# SOC_-_MCU_DOMAIN.net
KiCad netlist of a schematic drawn in Altium Designer
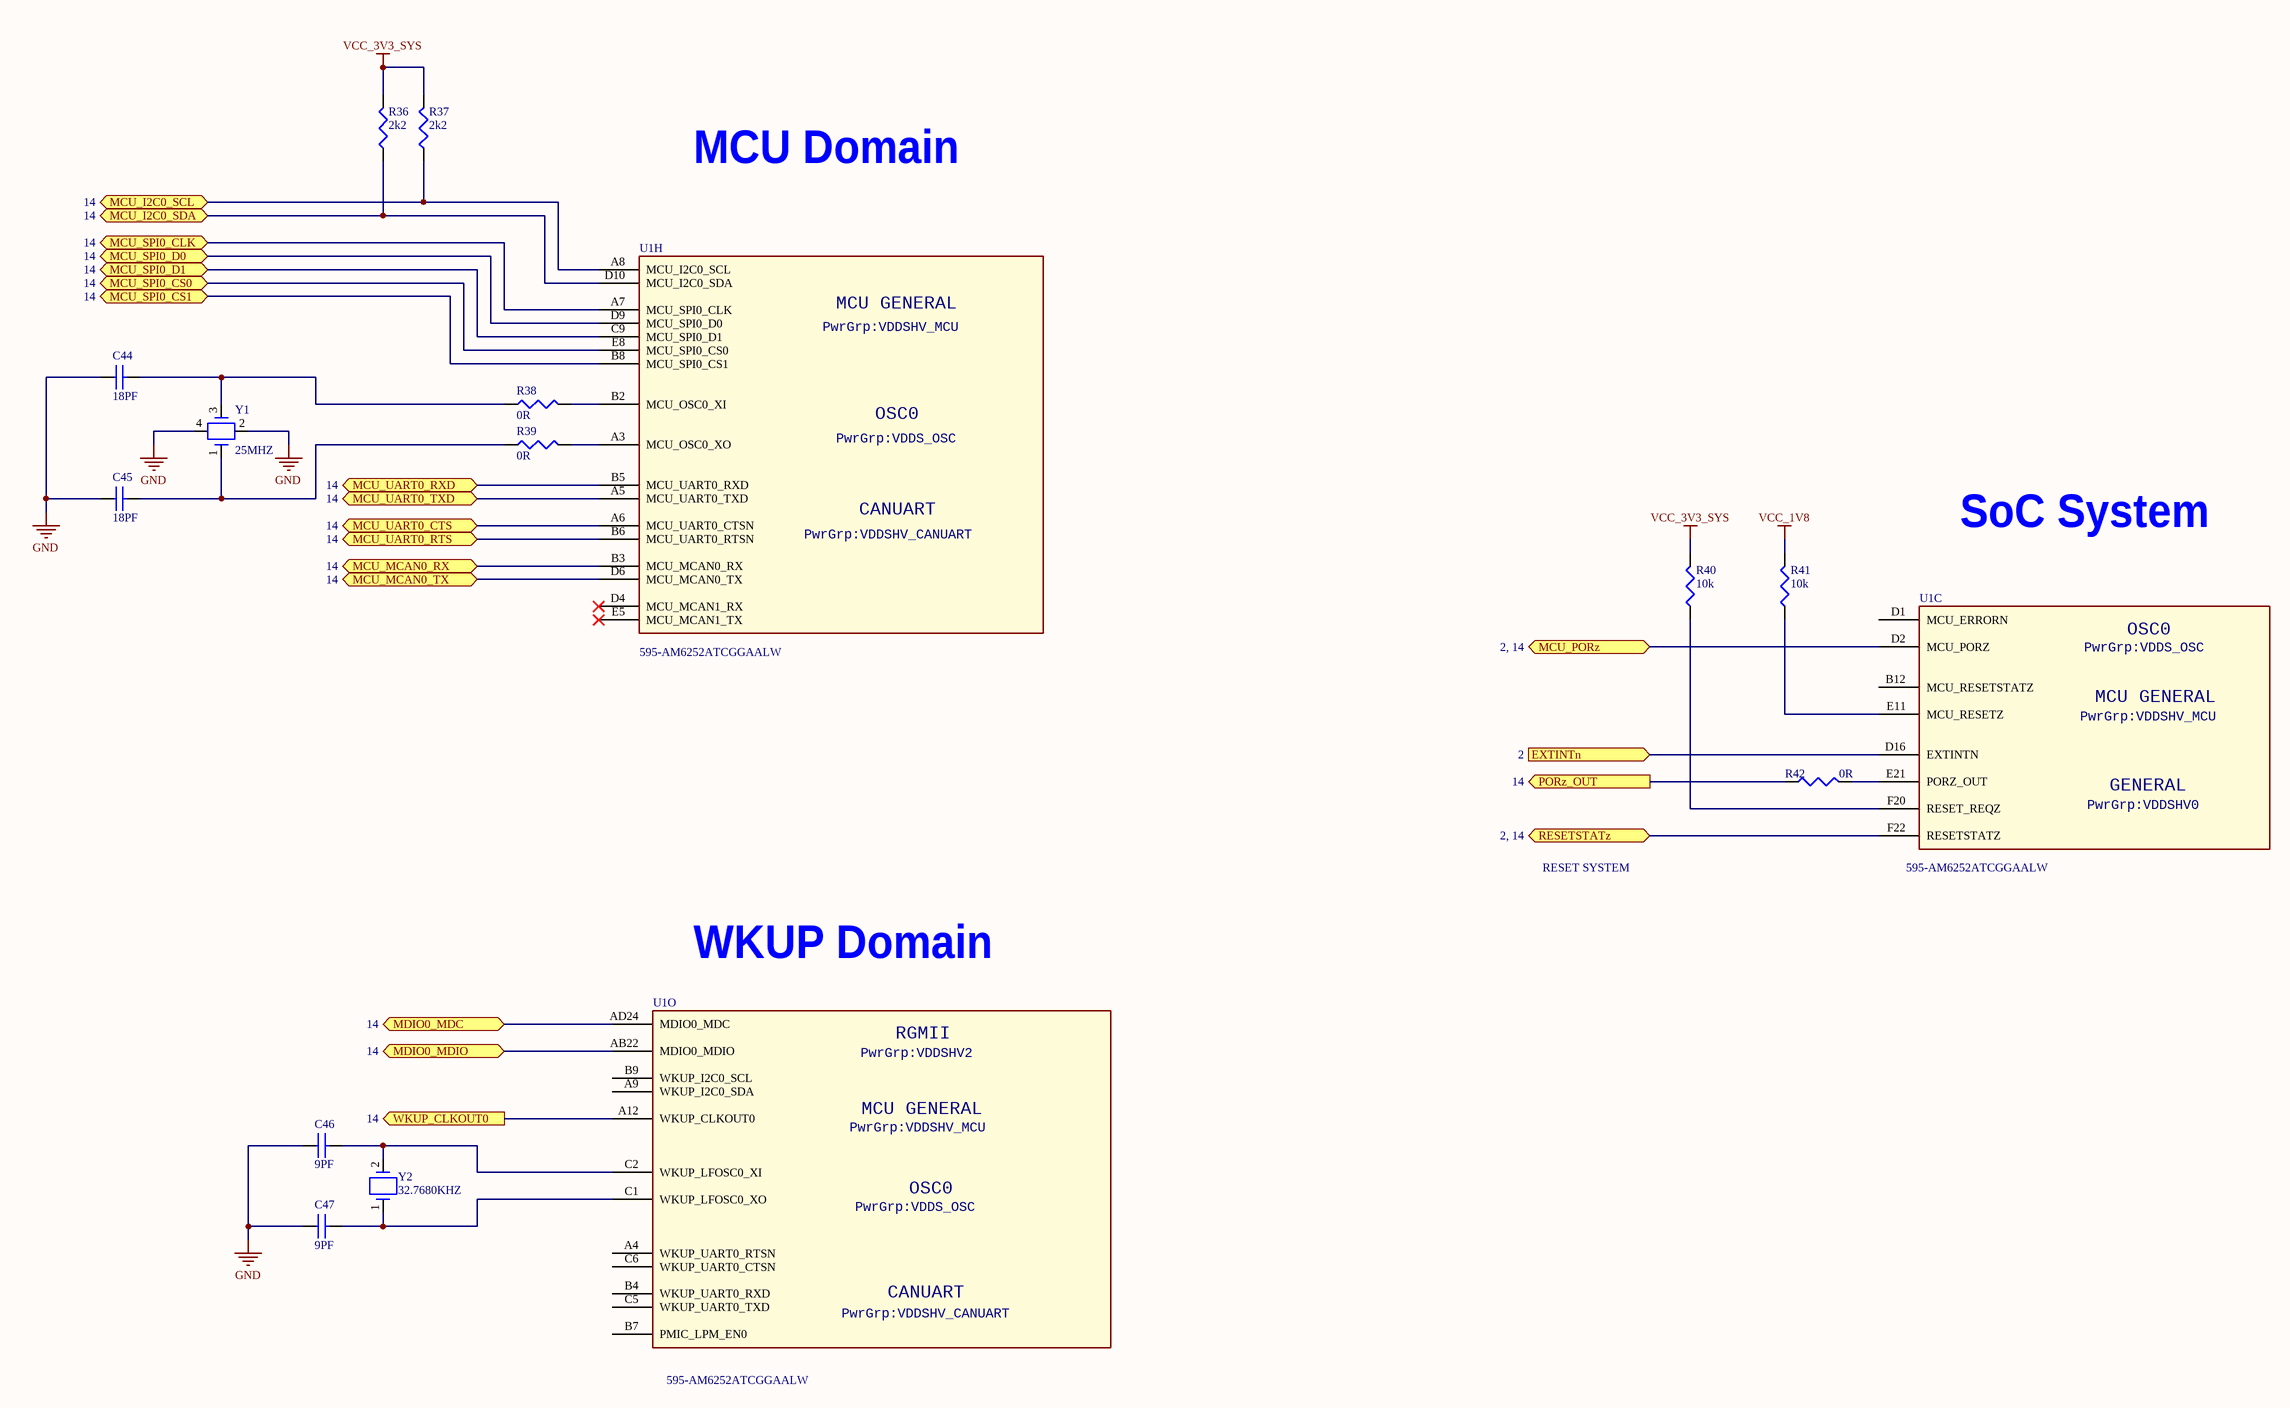
[diagram p0: SOC - MCU DOMAIN.SchDoc]

(export (version "E")
  (design (tool "Eeschema 10.0.6"))
  (components
    (comp (ref "C44")
      (value "18PF")
      (footprint "C0402")
      (description "CAP CER 18PF 50V C0G/NP0 0402")
      (fields
        (field (name "MANUFACTURER") "Murata")
        (field (name "MANUFACTURER PART NUMBER") "GJM1555C1H180JB01D")
      )
      (libsource (lib "Schlib AM625") (part "GJM1555C1H180JB01D"))
    )
    (comp (ref "C45")
      (value "18PF")
      (footprint "C0402")
      (description "CAP CER 18PF 50V C0G/NP0 0402")
      (fields
        (field (name "MANUFACTURER") "Murata")
        (field (name "MANUFACTURER PART NUMBER") "GJM1555C1H180JB01D")
      )
      (libsource (lib "Schlib AM625") (part "GJM1555C1H180JB01D"))
    )
    (comp (ref "C46")
      (value "9PF")
      (footprint "C0402")
      (description "CAP CER 9PF 50V C0G/NP0 0402")
      (fields
        (field (name "MANUFACTURER") "Murata")
        (field (name "MANUFACTURER PART NUMBER") "GJM1555C1H9R0DB01D")
      )
      (libsource (lib "Schlib AM625") (part "GJM1555C1H9R0DB01D"))
    )
    (comp (ref "C47")
      (value "9PF")
      (footprint "C0402")
      (description "CAP CER 9PF 50V C0G/NP0 0402")
      (fields
        (field (name "MANUFACTURER") "Murata")
        (field (name "MANUFACTURER PART NUMBER") "GJM1555C1H9R0DB01D")
      )
      (libsource (lib "Schlib AM625") (part "GJM1555C1H9R0DB01D"))
    )
    (comp (ref "R36")
      (value "2k2")
      (footprint "R0402")
      (description "RES 2.20K OHM 1/16W 1% 0402 SMD")
      (fields
        (field (name "MANUFACTURER") "Yageo")
        (field (name "MANUFACTURER PART NUMBER") "RC0402FR-072K2L")
      )
      (libsource (lib "Schlib AM625") (part "RC0402FR-072K2L"))
    )
    (comp (ref "R37")
      (value "2k2")
      (footprint "R0402")
      (description "RES 2.20K OHM 1/16W 1% 0402 SMD")
      (fields
        (field (name "MANUFACTURER") "Yageo")
        (field (name "MANUFACTURER PART NUMBER") "RC0402FR-072K2L")
      )
      (libsource (lib "Schlib AM625") (part "RC0402FR-072K2L"))
    )
    (comp (ref "R38")
      (value "0R")
      (footprint "R0402")
      (description "RES 0.0 OHM 1/16W 0402 SMD")
      (fields
        (field (name "MANUFACTURER") "Yageo")
        (field (name "MANUFACTURER PART NUMBER") "RC0402JR-070RL")
      )
      (libsource (lib "Schlib AM625") (part "RC0402JR-070RL"))
    )
    (comp (ref "R39")
      (value "0R")
      (footprint "R0402")
      (description "RES 0.0 OHM 1/16W 0402 SMD")
      (fields
        (field (name "MANUFACTURER") "Yageo")
        (field (name "MANUFACTURER PART NUMBER") "RC0402JR-070RL")
      )
      (libsource (lib "Schlib AM625") (part "RC0402JR-070RL"))
    )
    (comp (ref "R40")
      (value "10k")
      (footprint "R0201")
      (description "RES 10K OHM 1/20W 1% 0201 SMD")
      (fields
        (field (name "MANUFACTURER") "Yageo")
        (field (name "MANUFACTURER PART NUMBER") "RC0201FR-0710KL")
        (field (name ".CREATOR") "MM")
        (field (name ".CHECKED PCB") "MM")
        (field (name ".CHECKED SCH") "MM")
      )
      (libsource (lib "Schlib AM625") (part "RC0201FR-0710KL"))
    )
    (comp (ref "R41")
      (value "10k")
      (footprint "R0201")
      (description "RES 10K OHM 1/20W 1% 0201 SMD")
      (fields
        (field (name "MANUFACTURER") "Yageo")
        (field (name "MANUFACTURER PART NUMBER") "RC0201FR-0710KL")
        (field (name ".CREATOR") "MM")
        (field (name ".CHECKED PCB") "MM")
        (field (name ".CHECKED SCH") "MM")
      )
      (libsource (lib "Schlib AM625") (part "RC0201FR-0710KL"))
    )
    (comp (ref "R42")
      (value "0R")
      (footprint "R0402")
      (description "RES 0.0 OHM 1/16W 0402 SMD")
      (fields
        (field (name "MANUFACTURER") "Yageo")
        (field (name "MANUFACTURER PART NUMBER") "RC0402JR-070RL")
      )
      (libsource (lib "Schlib AM625") (part "RC0402JR-070RL"))
    )
    (comp (ref "U1")
      (value "AM62-EVM_BGA425")
      (footprint "BGA425C50P25X25_1300X1300X89")
      (description "ARM® Cortex®-A53 Microprocessor IC Sitara™ 2 Core, 64-Bit 1.4GHz 425-FCCSP (13x13)")
      (fields
        (field (name "MANUFACTURER") "Texas Instruments")
        (field (name "MANUFACTURER PART NUMBER") "AM6252ATCGGAALW")
        (field (name "SUPPLIER PART NUMBER 1") "595-AM6252ATCGGAALW")
      )
      (libsource (lib "Schlib AM625") (part "AM62-EVM_BGA425"))
    )
    (comp (ref "Y1")
      (value "25MHZ")
      (footprint "XRCGB25M000F3M00R0")
      (description "CRYSTAL 25.0000MHZ 6PF SMD")
      (fields
        (field (name "MANUFACTURER") "Murata")
        (field (name "MANUFACTURER PART NUMBER") "XRCGB25M000F3M00R0")
      )
      (libsource (lib "Schlib AM625") (part "XRCGB25M000F3M00R0"))
    )
    (comp (ref "Y2")
      (value "32.7680KHZ")
      (footprint "ECS327934QSTR")
      (description "CRYSTAL 32.7680KHZ 9PF SMD")
      (fields
        (field (name "MANUFACTURER") "ECS International")
        (field (name "MANUFACTURER PART NUMBER") "ECS-.327-9-34QCS-TR")
      )
      (libsource (lib "Schlib AM625") (part "ECS-.327-9-34QCS-TR"))
    )
  )
  (nets
    (net (code "1") (name "/EXTINTn") (class "Default")
      (node (ref "U1") (pin "D16") (pinfunction "EXTINTN_D16") (pintype "passive"))
    )
    (net (code "2") (name "/MCU_I2C0_SCL") (class "Default")
      (node (ref "R37") (pin "1") (pinfunction "1_1") (pintype "passive"))
      (node (ref "U1") (pin "A8") (pinfunction "MCU_I2C0_SCL_A8") (pintype "passive"))
    )
    (net (code "3") (name "/MCU_I2C0_SDA") (class "Default")
      (node (ref "R36") (pin "1") (pinfunction "1_1") (pintype "passive"))
      (node (ref "U1") (pin "D10") (pinfunction "MCU_I2C0_SDA_D10") (pintype "passive"))
    )
    (net (code "4") (name "/MCU_MCAN0_RX") (class "Default")
      (node (ref "U1") (pin "B3") (pinfunction "MCU_MCAN0_RX_B3") (pintype "passive"))
    )
    (net (code "5") (name "/MCU_MCAN0_TX") (class "Default")
      (node (ref "U1") (pin "D6") (pinfunction "MCU_MCAN0_TX_D6") (pintype "passive"))
    )
    (net (code "6") (name "/MCU_PORz") (class "Default")
      (node (ref "U1") (pin "D2") (pinfunction "MCU_PORZ_D2") (pintype "passive"))
    )
    (net (code "7") (name "/MCU_SPI0_CLK") (class "Default")
      (node (ref "U1") (pin "A7") (pinfunction "MCU_SPI0_CLK_A7") (pintype "passive"))
    )
    (net (code "8") (name "/MCU_SPI0_CS0") (class "Default")
      (node (ref "U1") (pin "E8") (pinfunction "MCU_SPI0_CS0_E8") (pintype "passive"))
    )
    (net (code "9") (name "/MCU_SPI0_CS1") (class "Default")
      (node (ref "U1") (pin "B8") (pinfunction "MCU_SPI0_CS1_B8") (pintype "passive"))
    )
    (net (code "10") (name "/MCU_SPI0_D0") (class "Default")
      (node (ref "U1") (pin "D9") (pinfunction "MCU_SPI0_D0_D9") (pintype "passive"))
    )
    (net (code "11") (name "/MCU_SPI0_D1") (class "Default")
      (node (ref "U1") (pin "C9") (pinfunction "MCU_SPI0_D1_C9") (pintype "passive"))
    )
    (net (code "12") (name "/MCU_UART0_CTS") (class "Default")
      (node (ref "U1") (pin "A6") (pinfunction "MCU_UART0_CTSN_A6") (pintype "passive"))
    )
    (net (code "13") (name "/MCU_UART0_RTS") (class "Default")
      (node (ref "U1") (pin "B6") (pinfunction "MCU_UART0_RTSN_B6") (pintype "passive"))
    )
    (net (code "14") (name "/MCU_UART0_RXD") (class "Default")
      (node (ref "U1") (pin "B5") (pinfunction "MCU_UART0_RXD_B5") (pintype "passive"))
    )
    (net (code "15") (name "/MCU_UART0_TXD") (class "Default")
      (node (ref "U1") (pin "A5") (pinfunction "MCU_UART0_TXD_A5") (pintype "passive"))
    )
    (net (code "16") (name "/MDIO0_MDC") (class "Default")
      (node (ref "U1") (pin "AD24") (pinfunction "MDIO0_MDC_AD24") (pintype "passive"))
    )
    (net (code "17") (name "/MDIO0_MDIO") (class "Default")
      (node (ref "U1") (pin "AB22") (pinfunction "MDIO0_MDIO_AB22") (pintype "passive"))
    )
    (net (code "18") (name "/PORz_OUT") (class "Default")
      (node (ref "R42") (pin "1") (pinfunction "1_1") (pintype "passive"))
    )
    (net (code "19") (name "/RESETSTATz") (class "Default")
      (node (ref "U1") (pin "F22") (pinfunction "RESETSTATZ_F22") (pintype "passive"))
    )
    (net (code "20") (name "/WKUP_CLKOUT0") (class "Default")
      (node (ref "U1") (pin "A12") (pinfunction "WKUP_CLKOUT0_A12") (pintype "passive"))
    )
    (net (code "21") (name "GND") (class "Default")
      (node (ref "C44") (pin "1") (pinfunction "1_1") (pintype "passive"))
      (node (ref "C45") (pin "1") (pinfunction "1_1") (pintype "passive"))
      (node (ref "C46") (pin "1") (pinfunction "1_1") (pintype "passive"))
      (node (ref "C47") (pin "1") (pinfunction "1_1") (pintype "passive"))
      (node (ref "Y1") (pin "2") (pinfunction "2_2") (pintype "passive"))
      (node (ref "Y1") (pin "4") (pinfunction "4_4") (pintype "passive"))
    )
    (net (code "22") (name "Net-(C44-Pad2)") (class "Default")
      (node (ref "C44") (pin "2") (pinfunction "2_2") (pintype "passive"))
      (node (ref "R38") (pin "1") (pinfunction "1_1") (pintype "passive"))
      (node (ref "Y1") (pin "3") (pinfunction "3_3") (pintype "passive"))
    )
    (net (code "23") (name "Net-(C45-Pad2)") (class "Default")
      (node (ref "C45") (pin "2") (pinfunction "2_2") (pintype "passive"))
      (node (ref "R39") (pin "1") (pinfunction "1_1") (pintype "passive"))
      (node (ref "Y1") (pin "1") (pinfunction "1_1") (pintype "passive"))
    )
    (net (code "24") (name "Net-(U1C-MCU_RESETZ)") (class "Default")
      (node (ref "R41") (pin "1") (pinfunction "1_1") (pintype "passive"))
      (node (ref "U1") (pin "E11") (pinfunction "MCU_RESETZ_E11") (pintype "passive"))
    )
    (net (code "25") (name "Net-(U1C-PORZ_OUT)") (class "Default")
      (node (ref "R42") (pin "2") (pinfunction "2_2") (pintype "passive"))
      (node (ref "U1") (pin "E21") (pinfunction "PORZ_OUT_E21") (pintype "passive"))
    )
    (net (code "26") (name "Net-(U1C-RESET_REQZ)") (class "Default")
      (node (ref "R40") (pin "1") (pinfunction "1_1") (pintype "passive"))
      (node (ref "U1") (pin "F20") (pinfunction "RESET_REQZ_F20") (pintype "passive"))
    )
    (net (code "27") (name "Net-(U1H-MCU_OSC0_XI)") (class "Default")
      (node (ref "R38") (pin "2") (pinfunction "2_2") (pintype "passive"))
      (node (ref "U1") (pin "B2") (pinfunction "MCU_OSC0_XI_B2") (pintype "passive"))
    )
    (net (code "28") (name "Net-(U1H-MCU_OSC0_XO)") (class "Default")
      (node (ref "R39") (pin "2") (pinfunction "2_2") (pintype "passive"))
      (node (ref "U1") (pin "A3") (pinfunction "MCU_OSC0_XO_A3") (pintype "passive"))
    )
    (net (code "29") (name "Net-(U1O-WKUP_LFOSC0_XI)") (class "Default")
      (node (ref "C46") (pin "2") (pinfunction "2_2") (pintype "passive"))
      (node (ref "U1") (pin "C2") (pinfunction "WKUP_LFOSC0_XI_C2") (pintype "passive"))
      (node (ref "Y2") (pin "2") (pinfunction "2_2") (pintype "passive"))
    )
    (net (code "30") (name "Net-(U1O-WKUP_LFOSC0_XO)") (class "Default")
      (node (ref "C47") (pin "2") (pinfunction "2_2") (pintype "passive"))
      (node (ref "U1") (pin "C1") (pinfunction "WKUP_LFOSC0_XO_C1") (pintype "passive"))
      (node (ref "Y2") (pin "1") (pinfunction "1_1") (pintype "passive"))
    )
    (net (code "31") (name "VCC_1V8") (class "Default")
      (node (ref "R41") (pin "2") (pinfunction "2_2") (pintype "passive"))
    )
    (net (code "32") (name "VCC_3V3_SYS") (class "Default")
      (node (ref "R36") (pin "2") (pinfunction "2_2") (pintype "passive"))
      (node (ref "R37") (pin "2") (pinfunction "2_2") (pintype "passive"))
      (node (ref "R40") (pin "2") (pinfunction "2_2") (pintype "passive"))
    )
    (net (code "33") (name "unconnected-(U1C-MCU_ERRORN-PadD1)") (class "Default")
      (node (ref "U1") (pin "D1") (pinfunction "MCU_ERRORN_D1") (pintype "passive"))
    )
    (net (code "34") (name "unconnected-(U1C-MCU_RESETSTATZ-PadB12)") (class "Default")
      (node (ref "U1") (pin "B12") (pinfunction "MCU_RESETSTATZ_B12") (pintype "passive"))
    )
    (net (code "35") (name "unconnected-(U1H-MCU_MCAN1_RX-PadD4)") (class "Default")
      (node (ref "U1") (pin "D4") (pinfunction "MCU_MCAN1_RX_D4") (pintype "passive+no_connect"))
    )
    (net (code "36") (name "unconnected-(U1H-MCU_MCAN1_TX-PadE5)") (class "Default")
      (node (ref "U1") (pin "E5") (pinfunction "MCU_MCAN1_TX_E5") (pintype "passive+no_connect"))
    )
    (net (code "37") (name "unconnected-(U1O-PMIC_LPM_EN0-PadB7)") (class "Default")
      (node (ref "U1") (pin "B7") (pinfunction "PMIC_LPM_EN0_B7") (pintype "passive"))
    )
    (net (code "38") (name "unconnected-(U1O-WKUP_I2C0_SCL-PadB9)") (class "Default")
      (node (ref "U1") (pin "B9") (pinfunction "WKUP_I2C0_SCL_B9") (pintype "passive"))
    )
    (net (code "39") (name "unconnected-(U1O-WKUP_I2C0_SDA-PadA9)") (class "Default")
      (node (ref "U1") (pin "A9") (pinfunction "WKUP_I2C0_SDA_A9") (pintype "passive"))
    )
    (net (code "40") (name "unconnected-(U1O-WKUP_UART0_CTSN-PadC6)") (class "Default")
      (node (ref "U1") (pin "C6") (pinfunction "WKUP_UART0_CTSN_C6") (pintype "passive"))
    )
    (net (code "41") (name "unconnected-(U1O-WKUP_UART0_RTSN-PadA4)") (class "Default")
      (node (ref "U1") (pin "A4") (pinfunction "WKUP_UART0_RTSN_A4") (pintype "passive"))
    )
    (net (code "42") (name "unconnected-(U1O-WKUP_UART0_RXD-PadB4)") (class "Default")
      (node (ref "U1") (pin "B4") (pinfunction "WKUP_UART0_RXD_B4") (pintype "passive"))
    )
    (net (code "43") (name "unconnected-(U1O-WKUP_UART0_TXD-PadC5)") (class "Default")
      (node (ref "U1") (pin "C5") (pinfunction "WKUP_UART0_TXD_C5") (pintype "passive"))
    )
  )
)
